# Connectors.net
KiCad netlist of a schematic drawn in Altium Designer
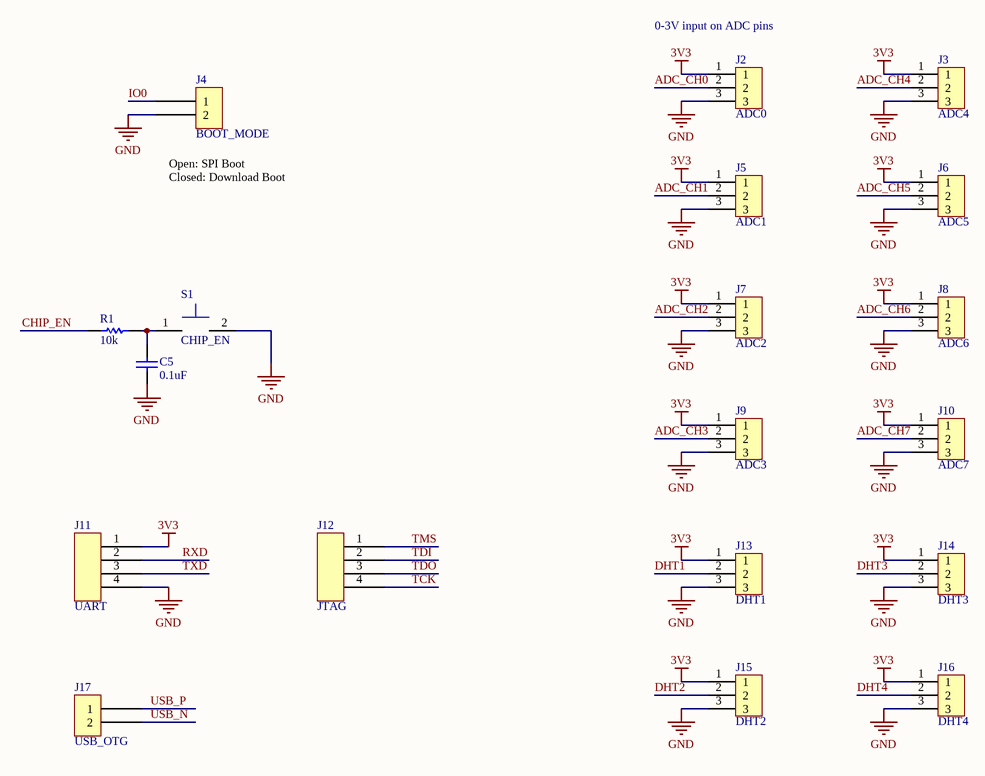
[diagram p0: Connectors.SchDoc]

(export (version "E")
  (design (tool "Eeschema 10.0.6"))
  (components
    (comp (ref "C5")
      (value "0.1uF")
      (footprint "PCB-oygqt4xf3sesynjclq4r-1")
      (description "0.1uF, ±10%, 50V, X7R, 0805, Multilayer Ceramic Capacitor")
      (fields (field (name "MANUFACTURER PART NUMBER") "CL21B104KBCNNNC"))
      (libsource (lib "CommunityVault") (part "SYM-94265da154d84be1-1"))
    )
    (comp (ref "J2")
      (value "ADC0")
      (footprint "PCB-xi9jnxfk0tsn3lp09zze-1")
      (description "Conn Unshrouded Header HDR 3 POS 2.54mm Solder ST Thru-Hole")
      (fields (field (name "MANUFACTURER PART NUMBER") "4-103321-5"))
      (libsource (lib "CommunityVault") (part "SYM-5821934eb82787e6-1"))
    )
    (comp (ref "J3")
      (value "ADC4")
      (footprint "PCB-xi9jnxfk0tsn3lp09zze-1")
      (description "Conn Unshrouded Header HDR 3 POS 2.54mm Solder ST Thru-Hole")
      (fields (field (name "MANUFACTURER PART NUMBER") "4-103321-5"))
      (libsource (lib "CommunityVault") (part "SYM-5821934eb82787e6-1"))
    )
    (comp (ref "J4")
      (value "BOOT_MODE")
      (footprint "Jumper")
      (description "2 pin male header straight tht")
      (libsource (lib "CommunityVault") (part "SYM-76d7babf30d4a910-1"))
    )
    (comp (ref "J5")
      (value "ADC1")
      (footprint "PCB-xi9jnxfk0tsn3lp09zze-1")
      (description "Conn Unshrouded Header HDR 3 POS 2.54mm Solder ST Thru-Hole")
      (fields (field (name "MANUFACTURER PART NUMBER") "4-103321-5"))
      (libsource (lib "CommunityVault") (part "SYM-5821934eb82787e6-1"))
    )
    (comp (ref "J6")
      (value "ADC5")
      (footprint "PCB-xi9jnxfk0tsn3lp09zze-1")
      (description "Conn Unshrouded Header HDR 3 POS 2.54mm Solder ST Thru-Hole")
      (fields (field (name "MANUFACTURER PART NUMBER") "4-103321-5"))
      (libsource (lib "CommunityVault") (part "SYM-5821934eb82787e6-1"))
    )
    (comp (ref "J7")
      (value "ADC2")
      (footprint "PCB-xi9jnxfk0tsn3lp09zze-1")
      (description "Conn Unshrouded Header HDR 3 POS 2.54mm Solder ST Thru-Hole")
      (fields (field (name "MANUFACTURER PART NUMBER") "4-103321-5"))
      (libsource (lib "CommunityVault") (part "SYM-5821934eb82787e6-1"))
    )
    (comp (ref "J8")
      (value "ADC6")
      (footprint "PCB-xi9jnxfk0tsn3lp09zze-1")
      (description "Conn Unshrouded Header HDR 3 POS 2.54mm Solder ST Thru-Hole")
      (fields (field (name "MANUFACTURER PART NUMBER") "4-103321-5"))
      (libsource (lib "CommunityVault") (part "SYM-5821934eb82787e6-1"))
    )
    (comp (ref "J9")
      (value "ADC3")
      (footprint "PCB-xi9jnxfk0tsn3lp09zze-1")
      (description "Conn Unshrouded Header HDR 3 POS 2.54mm Solder ST Thru-Hole")
      (fields (field (name "MANUFACTURER PART NUMBER") "4-103321-5"))
      (libsource (lib "CommunityVault") (part "SYM-5821934eb82787e6-1"))
    )
    (comp (ref "J10")
      (value "ADC7")
      (footprint "PCB-xi9jnxfk0tsn3lp09zze-1")
      (description "Conn Unshrouded Header HDR 3 POS 2.54mm Solder ST Thru-Hole")
      (fields (field (name "MANUFACTURER PART NUMBER") "4-103321-5"))
      (libsource (lib "CommunityVault") (part "SYM-5821934eb82787e6-1"))
    )
    (comp (ref "J11")
      (value "UART")
      (footprint "PCB-w7fgx0p37qyww1etoafk-1")
      (description "Conn Unshrouded Header HDR 4 POS 2.54mm Solder ST Thru-Hole KK?? Bag")
      (fields (field (name "MANUFACTURER PART NUMBER") "0022032041"))
      (libsource (lib "CommunityVault") (part "SYM-4df18464dcf59236-1"))
    )
    (comp (ref "J12")
      (value "JTAG")
      (footprint "PCB-w7fgx0p37qyww1etoafk-1")
      (description "Conn Unshrouded Header HDR 4 POS 2.54mm Solder ST Thru-Hole KK?? Bag")
      (fields (field (name "MANUFACTURER PART NUMBER") "0022032041"))
      (libsource (lib "CommunityVault") (part "SYM-4df18464dcf59236-1"))
    )
    (comp (ref "J13")
      (value "DHT1")
      (footprint "PCB-xi9jnxfk0tsn3lp09zze-1")
      (description "Conn Unshrouded Header HDR 3 POS 2.54mm Solder ST Thru-Hole")
      (fields (field (name "MANUFACTURER PART NUMBER") "4-103321-5"))
      (libsource (lib "CommunityVault") (part "SYM-5821934eb82787e6-1"))
    )
    (comp (ref "J14")
      (value "DHT3")
      (footprint "PCB-xi9jnxfk0tsn3lp09zze-1")
      (description "Conn Unshrouded Header HDR 3 POS 2.54mm Solder ST Thru-Hole")
      (fields (field (name "MANUFACTURER PART NUMBER") "4-103321-5"))
      (libsource (lib "CommunityVault") (part "SYM-5821934eb82787e6-1"))
    )
    (comp (ref "J15")
      (value "DHT2")
      (footprint "PCB-xi9jnxfk0tsn3lp09zze-1")
      (description "Conn Unshrouded Header HDR 3 POS 2.54mm Solder ST Thru-Hole")
      (fields (field (name "MANUFACTURER PART NUMBER") "4-103321-5"))
      (libsource (lib "CommunityVault") (part "SYM-5821934eb82787e6-1"))
    )
    (comp (ref "J16")
      (value "DHT4")
      (footprint "PCB-xi9jnxfk0tsn3lp09zze-1")
      (description "Conn Unshrouded Header HDR 3 POS 2.54mm Solder ST Thru-Hole")
      (fields (field (name "MANUFACTURER PART NUMBER") "4-103321-5"))
      (libsource (lib "CommunityVault") (part "SYM-5821934eb82787e6-1"))
    )
    (comp (ref "J17")
      (value "USB_OTG")
      (footprint "Jumper")
      (description "2 pin male header straight tht")
      (libsource (lib "CommunityVault") (part "CMP-08fac3900112d73d-14"))
    )
    (comp (ref "R1")
      (value "10k")
      (footprint "PCB-urbe6pl2f36u5sj9z9e0-1")
      (description "Res, AEC-Q200, Thick Film, 10K, 5%, 0603")
      (fields (field (name "MANUFACTURER PART NUMBER") "CRGCQ0603J10K"))
      (libsource (lib "CommunityVault") (part "SYM-1974d512ef63c6b3-1"))
    )
    (comp (ref "S1")
      (value "CHIP_EN")
      (footprint "PCB-xzcf6rj7v3ysitq80b7l-1")
      (description "Switch Tactile Spst-No 0.02a 15v")
      (libsource (lib "CommunityVault") (part "SYM-32abff024869ed6c-1"))
    )
  )
  (nets
    (net (code "1") (name "/ADC_CH0") (class "Default")
      (node (ref "J2") (pin "2") (pinfunction "2_2") (pintype "passive"))
    )
    (net (code "2") (name "/ADC_CH1") (class "Default")
      (node (ref "J5") (pin "2") (pinfunction "2_2") (pintype "passive"))
    )
    (net (code "3") (name "/ADC_CH2") (class "Default")
      (node (ref "J7") (pin "2") (pinfunction "2_2") (pintype "passive"))
    )
    (net (code "4") (name "/ADC_CH3") (class "Default")
      (node (ref "J9") (pin "2") (pinfunction "2_2") (pintype "passive"))
    )
    (net (code "5") (name "/ADC_CH4") (class "Default")
      (node (ref "J3") (pin "2") (pinfunction "2_2") (pintype "passive"))
    )
    (net (code "6") (name "/ADC_CH5") (class "Default")
      (node (ref "J6") (pin "2") (pinfunction "2_2") (pintype "passive"))
    )
    (net (code "7") (name "/ADC_CH6") (class "Default")
      (node (ref "J8") (pin "2") (pinfunction "2_2") (pintype "passive"))
    )
    (net (code "8") (name "/ADC_CH7") (class "Default")
      (node (ref "J10") (pin "2") (pinfunction "2_2") (pintype "passive"))
    )
    (net (code "9") (name "/CHIP_EN") (class "Default")
      (node (ref "R1") (pin "2") (pinfunction "2_2") (pintype "passive"))
    )
    (net (code "10") (name "/DHT1") (class "Default")
      (node (ref "J13") (pin "2") (pinfunction "2_2") (pintype "passive"))
    )
    (net (code "11") (name "/DHT2") (class "Default")
      (node (ref "J15") (pin "2") (pinfunction "2_2") (pintype "passive"))
    )
    (net (code "12") (name "/DHT3") (class "Default")
      (node (ref "J14") (pin "2") (pinfunction "2_2") (pintype "passive"))
    )
    (net (code "13") (name "/DHT4") (class "Default")
      (node (ref "J16") (pin "2") (pinfunction "2_2") (pintype "passive"))
    )
    (net (code "14") (name "/IO0") (class "Default")
      (node (ref "J4") (pin "1") (pinfunction "1_1") (pintype "power_in"))
    )
    (net (code "15") (name "/RXD") (class "Default")
      (node (ref "J11") (pin "2") (pinfunction "1_2") (pintype "passive"))
    )
    (net (code "16") (name "/TCK") (class "Default")
      (node (ref "J12") (pin "4") (pinfunction "1_4") (pintype "passive"))
    )
    (net (code "17") (name "/TDI") (class "Default")
      (node (ref "J12") (pin "2") (pinfunction "1_2") (pintype "passive"))
    )
    (net (code "18") (name "/TDO") (class "Default")
      (node (ref "J12") (pin "3") (pinfunction "1_3") (pintype "passive"))
    )
    (net (code "19") (name "/TMS") (class "Default")
      (node (ref "J12") (pin "1") (pinfunction "1_1") (pintype "passive"))
    )
    (net (code "20") (name "/TXD") (class "Default")
      (node (ref "J11") (pin "3") (pinfunction "1_3") (pintype "passive"))
    )
    (net (code "21") (name "/USB_N") (class "Default")
      (node (ref "J17") (pin "2") (pinfunction "2_2") (pintype "power_in"))
    )
    (net (code "22") (name "/USB_P") (class "Default")
      (node (ref "J17") (pin "1") (pinfunction "1_1") (pintype "power_in"))
    )
    (net (code "23") (name "3V3") (class "Default")
      (node (ref "J10") (pin "1") (pinfunction "1_1") (pintype "passive"))
      (node (ref "J11") (pin "1") (pinfunction "1_1") (pintype "passive"))
      (node (ref "J13") (pin "1") (pinfunction "1_1") (pintype "passive"))
      (node (ref "J14") (pin "1") (pinfunction "1_1") (pintype "passive"))
      (node (ref "J15") (pin "1") (pinfunction "1_1") (pintype "passive"))
      (node (ref "J16") (pin "1") (pinfunction "1_1") (pintype "passive"))
      (node (ref "J2") (pin "1") (pinfunction "1_1") (pintype "passive"))
      (node (ref "J3") (pin "1") (pinfunction "1_1") (pintype "passive"))
      (node (ref "J5") (pin "1") (pinfunction "1_1") (pintype "passive"))
      (node (ref "J6") (pin "1") (pinfunction "1_1") (pintype "passive"))
      (node (ref "J7") (pin "1") (pinfunction "1_1") (pintype "passive"))
      (node (ref "J8") (pin "1") (pinfunction "1_1") (pintype "passive"))
      (node (ref "J9") (pin "1") (pinfunction "1_1") (pintype "passive"))
    )
    (net (code "24") (name "GND") (class "Default")
      (node (ref "C5") (pin "1") (pinfunction "1_1") (pintype "passive"))
      (node (ref "J10") (pin "3") (pinfunction "3_3") (pintype "passive"))
      (node (ref "J11") (pin "4") (pinfunction "1_4") (pintype "passive"))
      (node (ref "J13") (pin "3") (pinfunction "3_3") (pintype "passive"))
      (node (ref "J14") (pin "3") (pinfunction "3_3") (pintype "passive"))
      (node (ref "J15") (pin "3") (pinfunction "3_3") (pintype "passive"))
      (node (ref "J16") (pin "3") (pinfunction "3_3") (pintype "passive"))
      (node (ref "J2") (pin "3") (pinfunction "3_3") (pintype "passive"))
      (node (ref "J3") (pin "3") (pinfunction "3_3") (pintype "passive"))
      (node (ref "J4") (pin "2") (pinfunction "2_2") (pintype "power_in"))
      (node (ref "J5") (pin "3") (pinfunction "3_3") (pintype "passive"))
      (node (ref "J6") (pin "3") (pinfunction "3_3") (pintype "passive"))
      (node (ref "J7") (pin "3") (pinfunction "3_3") (pintype "passive"))
      (node (ref "J8") (pin "3") (pinfunction "3_3") (pintype "passive"))
      (node (ref "J9") (pin "3") (pinfunction "3_3") (pintype "passive"))
      (node (ref "S1") (pin "2") (pinfunction "2_2") (pintype "power_in"))
    )
    (net (code "25") (name "Net-(C5-Pad2)") (class "Default")
      (node (ref "C5") (pin "2") (pinfunction "2_2") (pintype "passive"))
      (node (ref "R1") (pin "1") (pinfunction "1_1") (pintype "passive"))
      (node (ref "S1") (pin "1") (pinfunction "1_1") (pintype "power_in"))
    )
  )
)
